# MotorDriver.net
KiCad netlist of a schematic drawn in Altium Designer
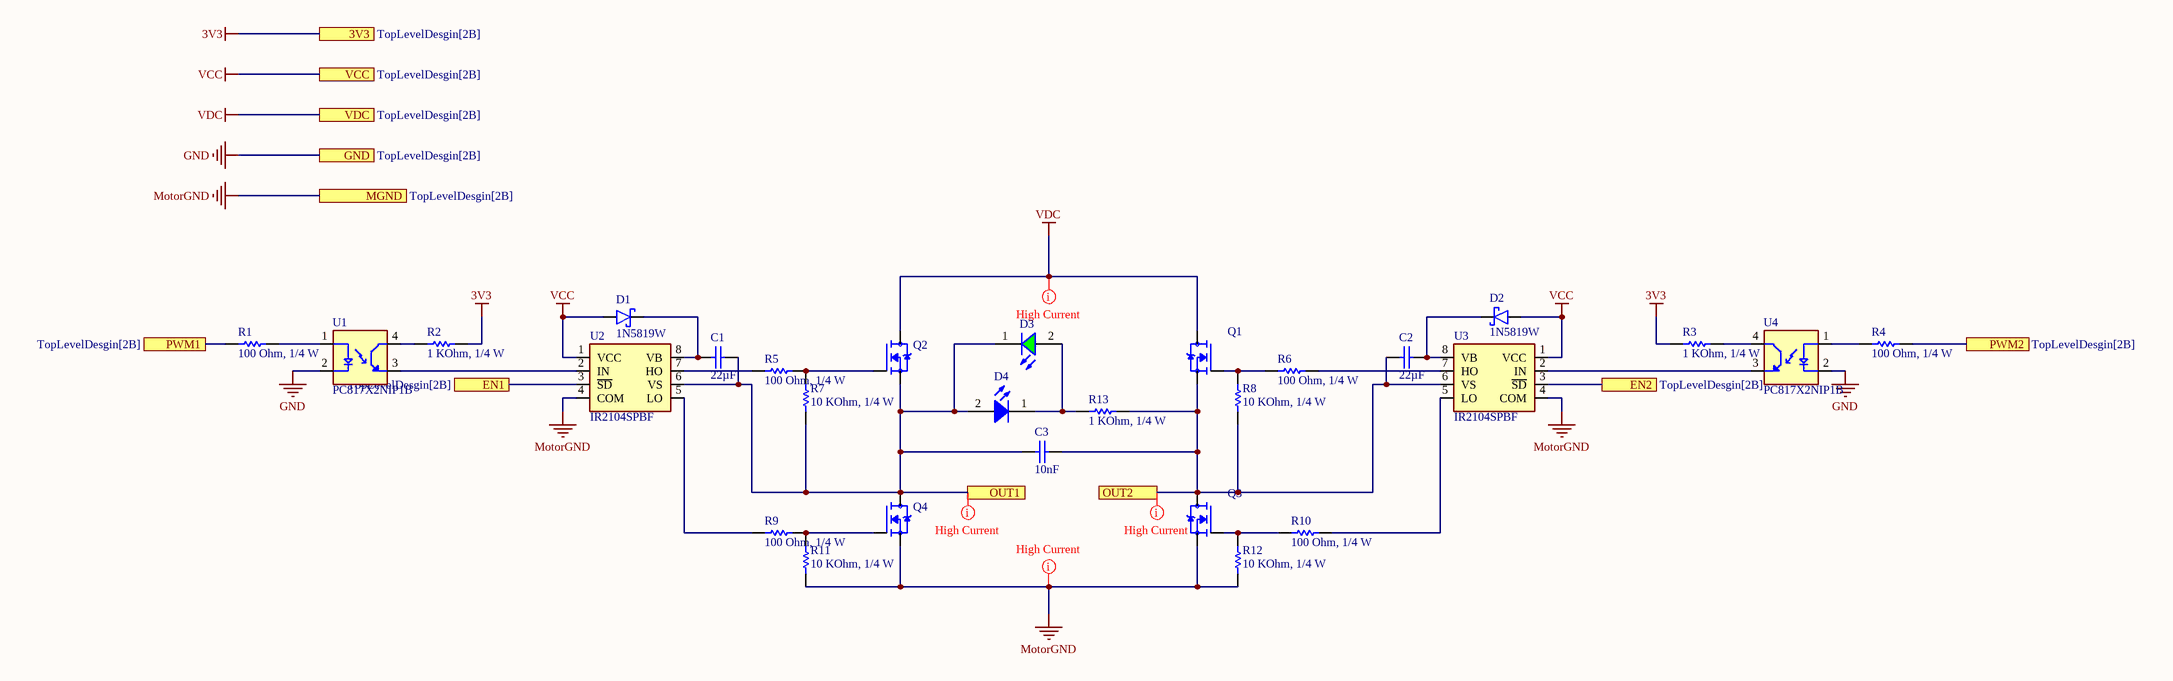
[diagram p0: MotorDriver.SchDoc]

(export (version "E")
  (design (tool "Eeschema 10.0.6"))
  (components
    (comp (ref "C1")
      (value "22µF")
      (footprint "CAP_0603")
      (description "CAP, size 0603, 22 uF, 6.3 VDC")
      (fields
        (field (name "TOLERANCE") "10%")
        (field (name "Comment") "010603226106.3")
        (field (name "SOURCE") "Capacitor_0603_10_percent.SchLib")
      )
      (libsource (lib "Tin Tran") (part "010603475106.3"))
    )
    (comp (ref "C2")
      (value "22µF")
      (footprint "CAP_0603")
      (description "CAP, size 0603, 22 uF, 6.3 VDC")
      (fields
        (field (name "TOLERANCE") "10%")
        (field (name "Comment") "010603226106.3")
        (field (name "SOURCE") "Capacitor_0603_10_percent.SchLib")
      )
      (libsource (lib "Tin Tran") (part "010603475106.3"))
    )
    (comp (ref "C3")
      (value "10nF")
      (footprint "CAP_0805")
      (description "CAP, size 0805, 10 nF, 50 VDC")
      (fields
        (field (name "TOLERANCE") "5%")
        (field (name "Comment") "0108051031050")
        (field (name "SOURCE") "Capacitor_0805_5_percent.SchLib")
      )
      (libsource (lib "Tin Tran") (part "0108058281050"))
    )
    (comp (ref "D1") (value "1N5819W") (footprint "1N5819W") (libsource (lib "Tin Tran") (part "1N5819W")))
    (comp (ref "D2") (value "1N5819W") (footprint "1N5819W") (libsource (lib "Tin Tran") (part "1N5819W")))
    (comp (ref "D3")
      (value "160603GreenClear")
      (footprint "WL-SMCW_0603_H=0.7mm")
      (description "WL-SMCW SMT Mono-color Chip LED Waterclear, size 0603, Green, 3.2V, 140deg")
      (libsource (lib "Tin Tran") (part "160603GreenClear"))
    )
    (comp (ref "D4")
      (value "160603BlueClear")
      (footprint "WL-SMCW_0603_H=0.7mm")
      (description "WL-SMCW SMT Mono-color Chip LED Waterclear, size 0603, Blue, 3.2V, 140deg")
      (libsource (lib "Tin Tran") (part "160603BlueClear"))
    )
    (comp (ref "Q1")
      (value "IRLR7843TRPBF")
      (footprint "TO229P990X239-3_4N")
      (description "RoHS Compliant")
      (fields (field (name "MF") "Infineon Technologies"))
      (libsource (lib "Tin Tran") (part "IRLR7843TRPBF"))
    )
    (comp (ref "Q2")
      (value "IRLR7843TRPBF")
      (footprint "TO229P990X239-3_4N")
      (description "RoHS Compliant")
      (fields (field (name "MF") "Infineon Technologies"))
      (libsource (lib "Tin Tran") (part "IRLR7843TRPBF"))
    )
    (comp (ref "Q3")
      (value "IRLR7843TRPBF")
      (footprint "TO229P990X239-3_4N")
      (description "RoHS Compliant")
      (fields (field (name "MF") "Infineon Technologies"))
      (libsource (lib "Tin Tran") (part "IRLR7843TRPBF"))
    )
    (comp (ref "Q4")
      (value "IRLR7843TRPBF")
      (footprint "TO229P990X239-3_4N")
      (description "RoHS Compliant")
      (fields (field (name "MF") "Infineon Technologies"))
      (libsource (lib "Tin Tran") (part "IRLR7843TRPBF"))
    )
    (comp (ref "R1")
      (value "100 Ohm, 1/4 W")
      (footprint "resistor_0603")
      (description "RES, size 0603, 100 Ohm, 1/4 W")
      (fields (field (name "Comment") "0006031011"))
      (libsource (lib "Tin Tran") (part "00060371541"))
    )
    (comp (ref "R2")
      (value "1 KOhm, 1/4 W")
      (footprint "resistor_0603")
      (description "RES, size 0603, 1 KOhm, 1/4 W")
      (fields (field (name "Comment") "0006031021"))
      (libsource (lib "Tin Tran") (part "00060371541"))
    )
    (comp (ref "R3")
      (value "1 KOhm, 1/4 W")
      (footprint "resistor_0603")
      (description "RES, size 0603, 1 KOhm, 1/4 W")
      (fields (field (name "Comment") "0006031021"))
      (libsource (lib "Tin Tran") (part "00060371541"))
    )
    (comp (ref "R4")
      (value "100 Ohm, 1/4 W")
      (footprint "resistor_0603")
      (description "RES, size 0603, 100 Ohm, 1/4 W")
      (fields (field (name "Comment") "0006031011"))
      (libsource (lib "Tin Tran") (part "00060371541"))
    )
    (comp (ref "R5")
      (value "100 Ohm, 1/4 W")
      (footprint "resistor_0603")
      (description "RES, size 0603, 100 Ohm, 1/4 W")
      (fields (field (name "Comment") "0006031011"))
      (libsource (lib "Tin Tran") (part "00060371541"))
    )
    (comp (ref "R6")
      (value "100 Ohm, 1/4 W")
      (footprint "resistor_0603")
      (description "RES, size 0603, 100 Ohm, 1/4 W")
      (fields (field (name "Comment") "0006031011"))
      (libsource (lib "Tin Tran") (part "00060371541"))
    )
    (comp (ref "R7")
      (value "10 KOhm, 1/4 W")
      (footprint "resistor_0603")
      (description "RES, size 0603, 10 KOhm, 1/4 W")
      (fields (field (name "Comment") "0006031031"))
      (libsource (lib "Tin Tran") (part "00060371541"))
    )
    (comp (ref "R8")
      (value "10 KOhm, 1/4 W")
      (footprint "resistor_0603")
      (description "RES, size 0603, 10 KOhm, 1/4 W")
      (fields (field (name "Comment") "0006031031"))
      (libsource (lib "Tin Tran") (part "00060371541"))
    )
    (comp (ref "R9")
      (value "100 Ohm, 1/4 W")
      (footprint "resistor_0603")
      (description "RES, size 0603, 100 Ohm, 1/4 W")
      (fields (field (name "Comment") "0006031011"))
      (libsource (lib "Tin Tran") (part "00060371541"))
    )
    (comp (ref "R10")
      (value "100 Ohm, 1/4 W")
      (footprint "resistor_0603")
      (description "RES, size 0603, 100 Ohm, 1/4 W")
      (fields (field (name "Comment") "0006031011"))
      (libsource (lib "Tin Tran") (part "00060371541"))
    )
    (comp (ref "R11")
      (value "10 KOhm, 1/4 W")
      (footprint "resistor_0603")
      (description "RES, size 0603, 10 KOhm, 1/4 W")
      (fields (field (name "Comment") "0006031031"))
      (libsource (lib "Tin Tran") (part "00060371541"))
    )
    (comp (ref "R12")
      (value "10 KOhm, 1/4 W")
      (footprint "resistor_0603")
      (description "RES, size 0603, 10 KOhm, 1/4 W")
      (fields (field (name "Comment") "0006031031"))
      (libsource (lib "Tin Tran") (part "00060371541"))
    )
    (comp (ref "R13")
      (value "1 KOhm, 1/4 W")
      (footprint "resistor_0603")
      (description "RES, size 0603, 1 KOhm, 1/4 W")
      (fields (field (name "Comment") "0006031021"))
      (libsource (lib "Tin Tran") (part "00060371541"))
    )
    (comp (ref "U1")
      (value "PC817X2NIP1B")
      (footprint "SOIC254P960X420-4N")
      (description "Optocoupler DC-IN 1-CH Transistor DC-OUT 4-Pin DIP SMD T/R")
      (fields (field (name "MF") "Sharp Microelectronics"))
      (libsource (lib "") (part "PC817X2NIP1B_1"))
    )
    (comp (ref "U2")
      (value "IR2104SPBF")
      (footprint "IR2104SPBF")
      (description "Half-Bridge Gate Driver IC Non-Inverting 8-SOIC")
      (fields (field (name "MF") "Infineon"))
      (libsource (lib "") (part "IR2104SPBF_1"))
    )
    (comp (ref "U3")
      (value "IR2104SPBF")
      (footprint "IR2104SPBF")
      (description "Half-Bridge Gate Driver IC Non-Inverting 8-SOIC")
      (fields (field (name "MF") "Infineon"))
      (libsource (lib "Tin Tran") (part "IR2104SPBF"))
    )
    (comp (ref "U4")
      (value "PC817X2NIP1B")
      (footprint "SOIC254P960X420-4N")
      (description "Optocoupler DC-IN 1-CH Transistor DC-OUT 4-Pin DIP SMD T/R")
      (fields (field (name "MF") "Sharp Microelectronics"))
      (libsource (lib "Tin Tran") (part "PC817X2NIP1B"))
    )
  )
  (nets
    (net (code "1") (name "/EN1") (class "Default")
      (node (ref "U2") (pin "3") (pinfunction "~{SD}_3") (pintype "bidirectional"))
    )
    (net (code "2") (name "/EN2") (class "Default")
      (node (ref "U3") (pin "3") (pinfunction "~{SD}_3") (pintype "bidirectional"))
    )
    (net (code "3") (name "/OUT1") (class "Default")
      (node (ref "C1") (pin "2") (pinfunction "2_2") (pintype "passive"))
      (node (ref "C3") (pin "1") (pinfunction "1_1") (pintype "passive"))
      (node (ref "D3") (pin "1") (pinfunction "K_1") (pintype "passive"))
      (node (ref "D4") (pin "2") (pinfunction "A_2") (pintype "passive"))
      (node (ref "Q2") (pin "3") (pinfunction "S_3") (pintype "passive"))
      (node (ref "Q4") (pin "4") (pinfunction "D_4") (pintype "passive"))
      (node (ref "R7") (pin "1") (pinfunction "1_1") (pintype "passive"))
      (node (ref "U2") (pin "6") (pinfunction "VS_6") (pintype "bidirectional"))
    )
    (net (code "4") (name "/OUT2") (class "Default")
      (node (ref "C2") (pin "1") (pinfunction "1_1") (pintype "passive"))
      (node (ref "C3") (pin "2") (pinfunction "2_2") (pintype "passive"))
      (node (ref "Q1") (pin "3") (pinfunction "S_3") (pintype "passive"))
      (node (ref "Q3") (pin "4") (pinfunction "D_4") (pintype "passive"))
      (node (ref "R13") (pin "2") (pinfunction "2_2") (pintype "passive"))
      (node (ref "R8") (pin "1") (pinfunction "1_1") (pintype "passive"))
      (node (ref "U3") (pin "6") (pinfunction "VS_6") (pintype "bidirectional"))
    )
    (net (code "5") (name "/PWM1") (class "Default")
      (node (ref "R1") (pin "1") (pinfunction "1_1") (pintype "passive"))
    )
    (net (code "6") (name "/PWM2") (class "Default")
      (node (ref "R4") (pin "2") (pinfunction "2_2") (pintype "passive"))
    )
    (net (code "7") (name "3V3") (class "Default")
      (node (ref "R2") (pin "2") (pinfunction "2_2") (pintype "passive"))
      (node (ref "R3") (pin "1") (pinfunction "1_1") (pintype "passive"))
    )
    (net (code "8") (name "GND") (class "Default")
      (node (ref "U1") (pin "2") (pinfunction "C_2") (pintype "passive"))
      (node (ref "U4") (pin "2") (pinfunction "C_2") (pintype "passive"))
    )
    (net (code "9") (name "MotorGND") (class "Default")
      (node (ref "Q3") (pin "3") (pinfunction "S_3") (pintype "passive"))
      (node (ref "Q4") (pin "3") (pinfunction "S_3") (pintype "passive"))
      (node (ref "R11") (pin "1") (pinfunction "1_1") (pintype "passive"))
      (node (ref "R12") (pin "1") (pinfunction "1_1") (pintype "passive"))
      (node (ref "U2") (pin "4") (pinfunction "COM_4") (pintype "bidirectional"))
      (node (ref "U3") (pin "4") (pinfunction "COM_4") (pintype "bidirectional"))
    )
    (net (code "10") (name "Net-(D3-A)") (class "Default")
      (node (ref "D3") (pin "2") (pinfunction "A_2") (pintype "passive"))
      (node (ref "D4") (pin "1") (pinfunction "K_1") (pintype "passive"))
      (node (ref "R13") (pin "1") (pinfunction "1_1") (pintype "passive"))
    )
    (net (code "11") (name "Net-(Q1-G)") (class "Default")
      (node (ref "Q1") (pin "1") (pinfunction "G_1") (pintype "passive"))
      (node (ref "R6") (pin "1") (pinfunction "1_1") (pintype "passive"))
      (node (ref "R8") (pin "2") (pinfunction "2_2") (pintype "passive"))
    )
    (net (code "12") (name "Net-(Q2-G)") (class "Default")
      (node (ref "Q2") (pin "1") (pinfunction "G_1") (pintype "passive"))
      (node (ref "R5") (pin "2") (pinfunction "2_2") (pintype "passive"))
      (node (ref "R7") (pin "2") (pinfunction "2_2") (pintype "passive"))
    )
    (net (code "13") (name "Net-(Q3-G)") (class "Default")
      (node (ref "Q3") (pin "1") (pinfunction "G_1") (pintype "passive"))
      (node (ref "R10") (pin "1") (pinfunction "1_1") (pintype "passive"))
      (node (ref "R12") (pin "2") (pinfunction "2_2") (pintype "passive"))
    )
    (net (code "14") (name "Net-(Q4-G)") (class "Default")
      (node (ref "Q4") (pin "1") (pinfunction "G_1") (pintype "passive"))
      (node (ref "R11") (pin "2") (pinfunction "2_2") (pintype "passive"))
      (node (ref "R9") (pin "2") (pinfunction "2_2") (pintype "passive"))
    )
    (net (code "15") (name "Net-(U1-A)") (class "Default")
      (node (ref "R1") (pin "2") (pinfunction "2_2") (pintype "passive"))
      (node (ref "U1") (pin "1") (pinfunction "A_1") (pintype "passive"))
    )
    (net (code "16") (name "Net-(U1-CT)") (class "Default")
      (node (ref "R2") (pin "1") (pinfunction "1_1") (pintype "passive"))
      (node (ref "U1") (pin "4") (pinfunction "CT_4") (pintype "passive"))
    )
    (net (code "17") (name "Net-(U1-ET)") (class "Default")
      (node (ref "U1") (pin "3") (pinfunction "ET_3") (pintype "passive"))
      (node (ref "U2") (pin "2") (pinfunction "IN_2") (pintype "bidirectional"))
    )
    (net (code "18") (name "Net-(U2-HO)") (class "Default")
      (node (ref "R5") (pin "1") (pinfunction "1_1") (pintype "passive"))
      (node (ref "U2") (pin "7") (pinfunction "HO_7") (pintype "bidirectional"))
    )
    (net (code "19") (name "Net-(U2-LO)") (class "Default")
      (node (ref "R9") (pin "1") (pinfunction "1_1") (pintype "passive"))
      (node (ref "U2") (pin "5") (pinfunction "LO_5") (pintype "bidirectional"))
    )
    (net (code "20") (name "Net-(U2-VB)") (class "Default")
      (node (ref "C1") (pin "1") (pinfunction "1_1") (pintype "passive"))
      (node (ref "D1") (pin "K") (pinfunction "K_K") (pintype "passive"))
      (node (ref "U2") (pin "8") (pinfunction "VB_8") (pintype "bidirectional"))
    )
    (net (code "21") (name "Net-(U3-HO)") (class "Default")
      (node (ref "R6") (pin "2") (pinfunction "2_2") (pintype "passive"))
      (node (ref "U3") (pin "7") (pinfunction "HO_7") (pintype "bidirectional"))
    )
    (net (code "22") (name "Net-(U3-IN)") (class "Default")
      (node (ref "U3") (pin "2") (pinfunction "IN_2") (pintype "bidirectional"))
      (node (ref "U4") (pin "3") (pinfunction "ET_3") (pintype "passive"))
    )
    (net (code "23") (name "Net-(U3-LO)") (class "Default")
      (node (ref "R10") (pin "2") (pinfunction "2_2") (pintype "passive"))
      (node (ref "U3") (pin "5") (pinfunction "LO_5") (pintype "bidirectional"))
    )
    (net (code "24") (name "Net-(U3-VB)") (class "Default")
      (node (ref "C2") (pin "2") (pinfunction "2_2") (pintype "passive"))
      (node (ref "D2") (pin "K") (pinfunction "K_K") (pintype "passive"))
      (node (ref "U3") (pin "8") (pinfunction "VB_8") (pintype "bidirectional"))
    )
    (net (code "25") (name "Net-(U4-A)") (class "Default")
      (node (ref "R4") (pin "1") (pinfunction "1_1") (pintype "passive"))
      (node (ref "U4") (pin "1") (pinfunction "A_1") (pintype "passive"))
    )
    (net (code "26") (name "Net-(U4-CT)") (class "Default")
      (node (ref "R3") (pin "2") (pinfunction "2_2") (pintype "passive"))
      (node (ref "U4") (pin "4") (pinfunction "CT_4") (pintype "passive"))
    )
    (net (code "27") (name "VCC") (class "Default")
      (node (ref "D1") (pin "A") (pinfunction "A_A") (pintype "passive"))
      (node (ref "D2") (pin "A") (pinfunction "A_A") (pintype "passive"))
      (node (ref "U2") (pin "1") (pinfunction "VCC_1") (pintype "bidirectional"))
      (node (ref "U3") (pin "1") (pinfunction "VCC_1") (pintype "bidirectional"))
    )
    (net (code "28") (name "VDC") (class "Default")
      (node (ref "Q1") (pin "4") (pinfunction "D_4") (pintype "passive"))
      (node (ref "Q2") (pin "4") (pinfunction "D_4") (pintype "passive"))
    )
  )
)
